# uart_pc.net
KiCad netlist of a schematic drawn in EAGLE
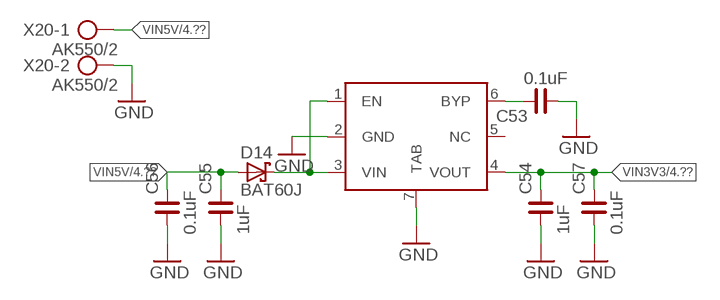
[diagram p0: schematic, sheet 1]
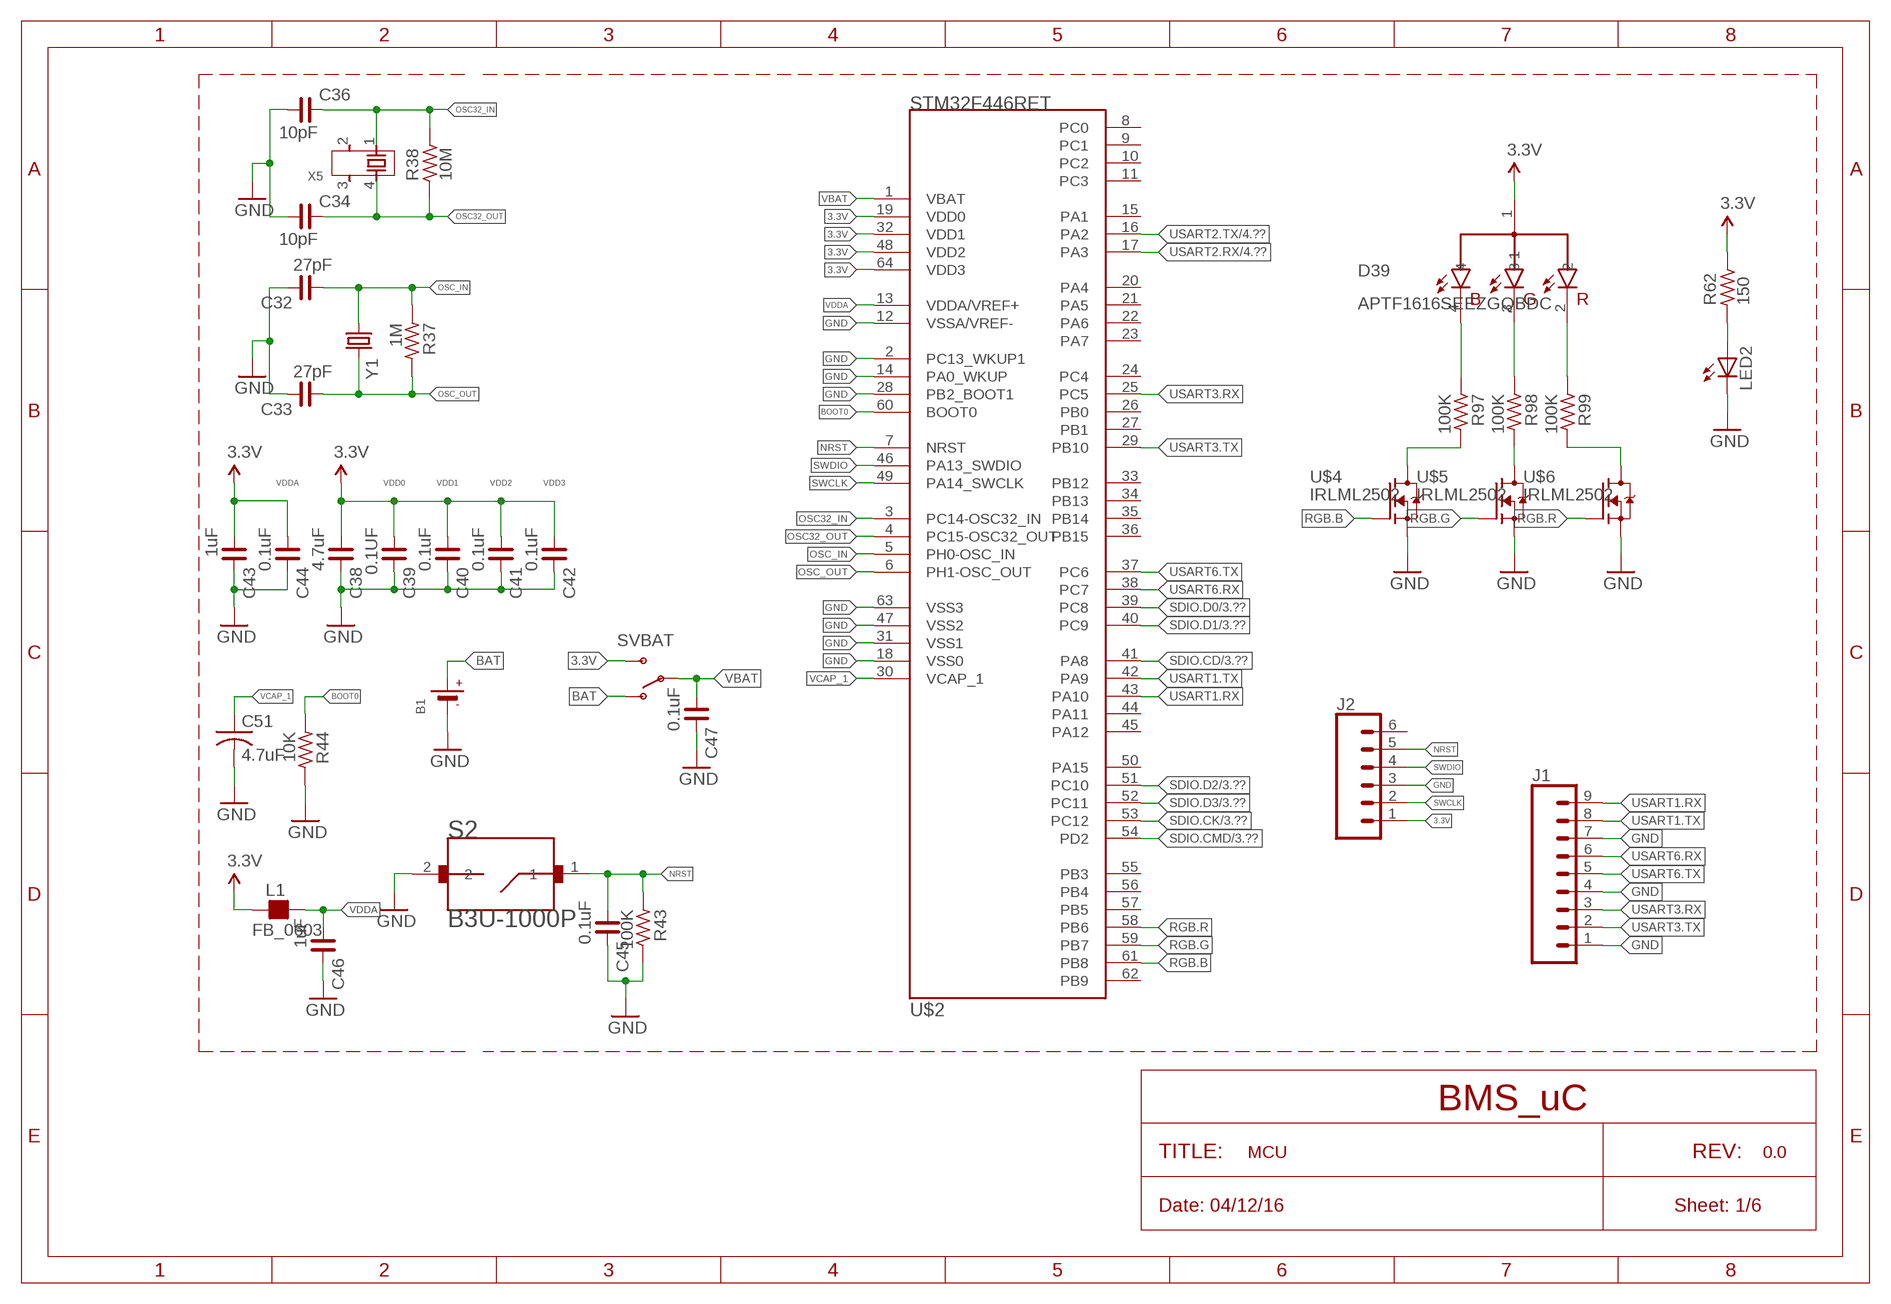
[diagram p1: schematic, sheet 2]
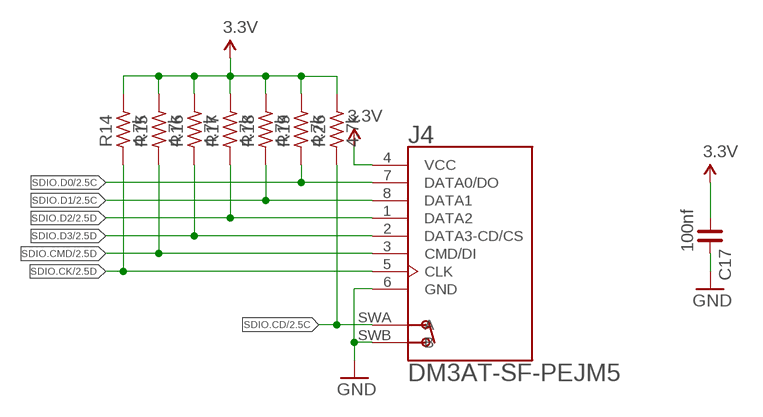
[diagram p2: schematic, sheet 3]
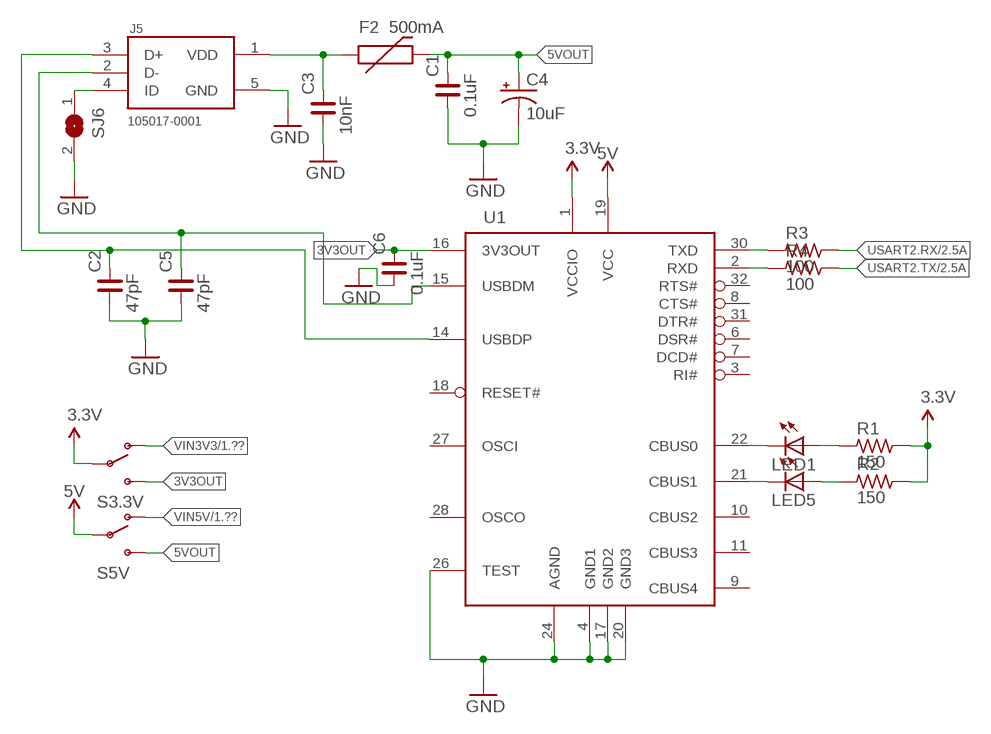
[diagram p3: schematic, sheet 4]

(export (version "E")
  (design (tool "Eeschema 10.0.6"))
  (components
    (comp (ref "C1")
      (value "0.1uF")
      (footprint "eagle-import:C0603")
      (libsource (lib "eagle-import") (part "C_0603"))
    )
    (comp (ref "C2")
      (value "47pF")
      (footprint "eagle-import:C0603")
      (libsource (lib "eagle-import") (part "C_0603"))
    )
    (comp (ref "C3")
      (value "10nF")
      (footprint "eagle-import:C0603")
      (libsource (lib "eagle-import") (part "C_0603"))
    )
    (comp (ref "C4")
      (value "10uF")
      (footprint "eagle-import:EIA3216")
      (libsource (lib "eagle-import") (part "10UF-16V-10%(TANT)"))
    )
    (comp (ref "C5")
      (value "47pF")
      (footprint "eagle-import:C0603")
      (libsource (lib "eagle-import") (part "C_0603"))
    )
    (comp (ref "C6")
      (value "0.1uF")
      (footprint "eagle-import:C0603")
      (libsource (lib "eagle-import") (part "C_0603"))
    )
    (comp (ref "F2")
      (value "500mA")
      (footprint "eagle-import:PTC-1206")
      (libsource (lib "eagle-import") (part "PTCSMD"))
    )
    (comp (ref "J5")
      (value "105017-0001")
      (footprint "eagle-import:MOLEX_105017-0001")
      (fields (field (name "MF") "Molex"))
      (libsource (lib "eagle-import") (part "105017-0001"))
    )
    (comp (ref "LED1")
      (value "LEDCHIPLED_0603")
      (footprint "eagle-import:CHIPLED_0603")
      (libsource (lib "eagle-import") (part "LEDCHIPLED_0603"))
    )
    (comp (ref "LED5")
      (value "LEDCHIPLED_0603")
      (footprint "eagle-import:CHIPLED_0603")
      (libsource (lib "eagle-import") (part "LEDCHIPLED_0603"))
    )
    (comp (ref "R1")
      (value "150")
      (footprint "eagle-import:R0603")
      (libsource (lib "eagle-import") (part "R_0603"))
    )
    (comp (ref "R2")
      (value "150")
      (footprint "eagle-import:R0603")
      (libsource (lib "eagle-import") (part "R_0603"))
    )
    (comp (ref "R3")
      (value "100")
      (footprint "eagle-import:R0603")
      (libsource (lib "eagle-import") (part "R_0603"))
    )
    (comp (ref "R4")
      (value "100")
      (footprint "eagle-import:R0603")
      (libsource (lib "eagle-import") (part "R_0603"))
    )
    (comp (ref "S3.3V")
      (value "SWITCH-SPDTSMD")
      (footprint "eagle-import:AYZ0202")
      (libsource (lib "eagle-import") (part "SWITCH-SPDTSMD"))
    )
    (comp (ref "S5V")
      (value "SWITCH-SPDTSMD")
      (footprint "eagle-import:AYZ0202")
      (libsource (lib "eagle-import") (part "SWITCH-SPDTSMD"))
    )
    (comp (ref "SJ6")
      (value "SOLDERJUMPER")
      (footprint "eagle-import:SOLDERJUMPER_ARROW_NOPASTE")
      (libsource (lib "eagle-import") (part "SOLDERJUMPER"))
    )
    (comp (ref "U1")
      (value "FT232RQ")
      (footprint "eagle-import:LQFP32")
      (fields (field (name "MF") "FTDI"))
      (libsource (lib "eagle-import") (part "FT232RQ"))
    )
    (comp (ref "C53")
      (value "0.1uF")
      (footprint "eagle-import:C0603")
      (libsource (lib "eagle-import") (part "C_0603"))
    )
    (comp (ref "C54")
      (value "1uF")
      (footprint "eagle-import:C0603")
      (libsource (lib "eagle-import") (part "C_0603"))
    )
    (comp (ref "C55")
      (value "1uF")
      (footprint "eagle-import:C0603")
      (libsource (lib "eagle-import") (part "C_0603"))
    )
    (comp (ref "C56")
      (value "0.1uF")
      (footprint "eagle-import:C0603")
      (libsource (lib "eagle-import") (part "C_0603"))
    )
    (comp (ref "C57")
      (value "0.1uF")
      (footprint "eagle-import:C0603")
      (libsource (lib "eagle-import") (part "C_0603"))
    )
    (comp (ref "D14")
      (value "BAT60J")
      (footprint "eagle-import:SOD323_ST")
      (libsource (lib "eagle-import") (part "BAT60J"))
    )
    (comp (ref "U$3")
      (value "MIC5353-3.3YMT-TR")
      (footprint "eagle-import:DFN-6_DC-L")
      (libsource (lib "eagle-import") (part "MIC5353-3.3YMT-TR"))
    )
    (comp (ref "X20")
      (value "AK550/2")
      (footprint "eagle-import:AK550_2")
      (libsource (lib "eagle-import") (part "AK550/2"))
    )
    (comp (ref "C17")
      (value "100nf")
      (footprint "eagle-import:C0603")
      (libsource (lib "eagle-import") (part "C_0603"))
    )
    (comp (ref "J4")
      (value "DM3AT-SF-PEJM5")
      (footprint "eagle-import:HRS_DM3AT-SF-PEJM5")
      (fields (field (name "MF") "Hirose"))
      (libsource (lib "eagle-import") (part "DM3AT-SF-PEJM5"))
    )
    (comp (ref "R14")
      (value "4.7k")
      (footprint "eagle-import:R0603")
      (libsource (lib "eagle-import") (part "R_0603"))
    )
    (comp (ref "R15")
      (value "4.7k")
      (footprint "eagle-import:R0603")
      (libsource (lib "eagle-import") (part "R_0603"))
    )
    (comp (ref "R16")
      (value "4.7k")
      (footprint "eagle-import:R0603")
      (libsource (lib "eagle-import") (part "R_0603"))
    )
    (comp (ref "R17")
      (value "4.7k")
      (footprint "eagle-import:R0603")
      (libsource (lib "eagle-import") (part "R_0603"))
    )
    (comp (ref "R18")
      (value "4.7k")
      (footprint "eagle-import:R0603")
      (libsource (lib "eagle-import") (part "R_0603"))
    )
    (comp (ref "R19")
      (value "4.7k")
      (footprint "eagle-import:R0603")
      (libsource (lib "eagle-import") (part "R_0603"))
    )
    (comp (ref "R26")
      (value "4.7k")
      (footprint "eagle-import:R0603")
      (libsource (lib "eagle-import") (part "R_0603"))
    )
    (comp (ref "B1")
      (value "BATTERYCR1220_SMT")
      (footprint "eagle-import:CR1220")
      (libsource (lib "eagle-import") (part "BATTERYCR1220_SMT"))
    )
    (comp (ref "C32")
      (value "27pF")
      (footprint "eagle-import:C0603")
      (libsource (lib "eagle-import") (part "C_0603"))
    )
    (comp (ref "C33")
      (value "27pF")
      (footprint "eagle-import:C0603")
      (libsource (lib "eagle-import") (part "C_0603"))
    )
    (comp (ref "C34")
      (value "10pF")
      (footprint "eagle-import:C0603")
      (libsource (lib "eagle-import") (part "C_0603"))
    )
    (comp (ref "C36")
      (value "10pF")
      (footprint "eagle-import:C0603")
      (libsource (lib "eagle-import") (part "C_0603"))
    )
    (comp (ref "C38")
      (value "4.7uF")
      (footprint "eagle-import:C0603")
      (libsource (lib "eagle-import") (part "C_0603"))
    )
    (comp (ref "C39")
      (value "0.1UF")
      (footprint "eagle-import:C0603")
      (libsource (lib "eagle-import") (part "C_0603"))
    )
    (comp (ref "C40")
      (value "0.1uF")
      (footprint "eagle-import:C0603")
      (libsource (lib "eagle-import") (part "C_0603"))
    )
    (comp (ref "C41")
      (value "0.1uF")
      (footprint "eagle-import:C0603")
      (libsource (lib "eagle-import") (part "C_0603"))
    )
    (comp (ref "C42")
      (value "0.1uF")
      (footprint "eagle-import:C0603")
      (libsource (lib "eagle-import") (part "C_0603"))
    )
    (comp (ref "C43")
      (value "1uF")
      (footprint "eagle-import:C0603")
      (libsource (lib "eagle-import") (part "C_0603"))
    )
    (comp (ref "C44")
      (value "0.1uF")
      (footprint "eagle-import:C0603")
      (libsource (lib "eagle-import") (part "C_0603"))
    )
    (comp (ref "C45")
      (value "0.1uF")
      (footprint "eagle-import:C0603")
      (libsource (lib "eagle-import") (part "C_0603"))
    )
    (comp (ref "C46")
      (value "1uF")
      (footprint "eagle-import:C0603")
      (libsource (lib "eagle-import") (part "C_0603"))
    )
    (comp (ref "C47")
      (value "0.1uF")
      (footprint "eagle-import:C0603")
      (libsource (lib "eagle-import") (part "C_0603"))
    )
    (comp (ref "C51")
      (value "4.7uF")
      (footprint "eagle-import:C1206")
      (libsource (lib "eagle-import") (part "C-USC1206"))
    )
    (comp (ref "D39")
      (value "APTF1616SEEZGQBDC")
      (footprint "eagle-import:0606(1616)")
      (fields (field (name "MF") "Lumex") (field (name "MP") "SML-LX0404SIUPGUSB"))
      (libsource (lib "eagle-import") (part "APTF1616SEEZGQBDC"))
    )
    (comp (ref "J1")
      (value "CONN_09")
      (footprint "eagle-import:1X09")
      (libsource (lib "eagle-import") (part "CONN_09"))
    )
    (comp (ref "J2")
      (value "CONN_06SILK_FEMALE_PTH")
      (footprint "eagle-import:1X06")
      (libsource (lib "eagle-import") (part "CONN_06SILK_FEMALE_PTH"))
    )
    (comp (ref "L1")
      (value "FB_0603")
      (footprint "eagle-import:L0603")
      (libsource (lib "eagle-import") (part "FB_0603"))
    )
    (comp (ref "LED2")
      (value "LEDCHIP-LED0603")
      (footprint "eagle-import:CHIP-LED0603")
      (libsource (lib "eagle-import") (part "LEDCHIP-LED0603"))
    )
    (comp (ref "R37")
      (value "1M")
      (footprint "eagle-import:R0603")
      (libsource (lib "eagle-import") (part "R_0603"))
    )
    (comp (ref "R38")
      (value "10M")
      (footprint "eagle-import:R0603")
      (libsource (lib "eagle-import") (part "R_0603"))
    )
    (comp (ref "R43")
      (value "100K")
      (footprint "eagle-import:R0603")
      (libsource (lib "eagle-import") (part "R_0603"))
    )
    (comp (ref "R44")
      (value "10K")
      (footprint "eagle-import:R0603")
      (libsource (lib "eagle-import") (part "R_0603"))
    )
    (comp (ref "R62")
      (value "150")
      (footprint "eagle-import:R0603")
      (libsource (lib "eagle-import") (part "R_0603"))
    )
    (comp (ref "R97")
      (value "100K")
      (footprint "eagle-import:R0603")
      (libsource (lib "eagle-import") (part "R_0603"))
    )
    (comp (ref "R98")
      (value "100K")
      (footprint "eagle-import:R0603")
      (libsource (lib "eagle-import") (part "R_0603"))
    )
    (comp (ref "R99")
      (value "100K")
      (footprint "eagle-import:R0603")
      (libsource (lib "eagle-import") (part "R_0603"))
    )
    (comp (ref "S2")
      (value "B3U-1000P")
      (footprint "eagle-import:SW_B3U-1000P")
      (fields (field (name "MF") "Omron"))
      (libsource (lib "eagle-import") (part "B3U-1000P"))
    )
    (comp (ref "SVBAT")
      (value "SWITCH-SPDTSMD")
      (footprint "eagle-import:AYZ0202")
      (libsource (lib "eagle-import") (part "SWITCH-SPDTSMD"))
    )
    (comp (ref "U$2")
      (value "STM32F446RET")
      (footprint "eagle-import:LQFP64")
      (libsource (lib "eagle-import") (part "STM32F446RET"))
    )
    (comp (ref "U$4")
      (value "IRLML2502")
      (footprint "eagle-import:SOT23")
      (fields (field (name "MF") "International Rectifier"))
      (libsource (lib "eagle-import") (part "IRLML2502"))
    )
    (comp (ref "U$5")
      (value "IRLML2502")
      (footprint "eagle-import:SOT23")
      (fields (field (name "MF") "International Rectifier"))
      (libsource (lib "eagle-import") (part "IRLML2502"))
    )
    (comp (ref "U$6")
      (value "IRLML2502")
      (footprint "eagle-import:SOT23")
      (fields (field (name "MF") "International Rectifier"))
      (libsource (lib "eagle-import") (part "IRLML2502"))
    )
    (comp (ref "X5")
      (value "CRYSTAL-4PIN")
      (footprint "eagle-import:ABRACON-ABS25-32.768KHZ")
      (libsource (lib "eagle-import") (part "CRYSTAL-4PIN"))
    )
    (comp (ref "Y1")
      (value "CRYSTALSMD")
      (footprint "eagle-import:HC49UP")
      (libsource (lib "eagle-import") (part "CRYSTALSMD"))
    )
  )
  (nets
    (net (code "1") (name "3.3V") (class "Default")
      (node (ref "C17") (pin "1") (pinfunction "1_1") (pintype "passive"))
      (node (ref "C38") (pin "1") (pinfunction "1_1") (pintype "passive"))
      (node (ref "C39") (pin "1") (pinfunction "1_1") (pintype "passive"))
      (node (ref "C40") (pin "1") (pinfunction "1_1") (pintype "passive"))
      (node (ref "C41") (pin "1") (pinfunction "1_1") (pintype "passive"))
      (node (ref "C42") (pin "1") (pinfunction "1_1") (pintype "passive"))
      (node (ref "C43") (pin "1") (pinfunction "1_1") (pintype "passive"))
      (node (ref "C44") (pin "1") (pinfunction "1_1") (pintype "passive"))
      (node (ref "D39") (pin "1") (pinfunction "1_1") (pintype "passive"))
      (node (ref "J2") (pin "1") (pinfunction "1_1") (pintype "passive"))
      (node (ref "J4") (pin "4") (pinfunction "VCC_4") (pintype "power_in"))
      (node (ref "L1") (pin "1") (pinfunction "1_1") (pintype "passive"))
      (node (ref "R1") (pin "2") (pinfunction "2_2") (pintype "passive"))
      (node (ref "R14") (pin "2") (pinfunction "2_2") (pintype "passive"))
      (node (ref "R15") (pin "2") (pinfunction "2_2") (pintype "passive"))
      (node (ref "R16") (pin "2") (pinfunction "2_2") (pintype "passive"))
      (node (ref "R17") (pin "2") (pinfunction "2_2") (pintype "passive"))
      (node (ref "R18") (pin "2") (pinfunction "2_2") (pintype "passive"))
      (node (ref "R19") (pin "2") (pinfunction "2_2") (pintype "passive"))
      (node (ref "R2") (pin "2") (pinfunction "2_2") (pintype "passive"))
      (node (ref "R26") (pin "2") (pinfunction "2_2") (pintype "passive"))
      (node (ref "R62") (pin "2") (pinfunction "2_2") (pintype "passive"))
      (node (ref "S3.3V") (pin "2") (pinfunction "P_2") (pintype "passive"))
      (node (ref "SVBAT") (pin "3") (pinfunction "S_3") (pintype "passive"))
      (node (ref "U$2") (pin "19") (pinfunction "VDD0_19") (pintype "power_in"))
      (node (ref "U$2") (pin "32") (pinfunction "VDD1_32") (pintype "power_in"))
      (node (ref "U$2") (pin "48") (pinfunction "VDD2_48") (pintype "power_in"))
      (node (ref "U$2") (pin "64") (pinfunction "VDD3_64") (pintype "power_in"))
      (node (ref "U1") (pin "1") (pinfunction "VCCIO_1") (pintype "power_in"))
    )
    (net (code "2") (name "3V3OUT") (class "Default")
      (node (ref "C6") (pin "2") (pinfunction "2_2") (pintype "passive"))
      (node (ref "S3.3V") (pin "3") (pinfunction "S_3") (pintype "passive"))
      (node (ref "U1") (pin "16") (pinfunction "3V3OUT_16") (pintype "output"))
    )
    (net (code "3") (name "5V") (class "Default")
      (node (ref "S5V") (pin "2") (pinfunction "P_2") (pintype "passive"))
      (node (ref "U1") (pin "19") (pinfunction "VCC_19") (pintype "power_in"))
    )
    (net (code "4") (name "5VOUT") (class "Default")
      (node (ref "C1") (pin "2") (pinfunction "2_2") (pintype "passive"))
      (node (ref "C4") (pin "A") (pinfunction "+_A") (pintype "passive"))
      (node (ref "F2") (pin "2") (pinfunction "2_2") (pintype "bidirectional"))
      (node (ref "S5V") (pin "3") (pinfunction "S_3") (pintype "passive"))
    )
    (net (code "5") (name "BAT") (class "Default")
      (node (ref "B1") (pin "+$1") (pinfunction "+_+$1") (pintype "passive"))
      (node (ref "SVBAT") (pin "1") (pinfunction "O_1") (pintype "passive"))
    )
    (net (code "6") (name "BOOT0") (class "Default")
      (node (ref "R44") (pin "1") (pinfunction "1_1") (pintype "passive"))
      (node (ref "U$2") (pin "60") (pinfunction "BOOT0_60") (pintype "input"))
    )
    (net (code "7") (name "GND") (class "Default")
      (node (ref "B1") (pin "-") (pinfunction "-_-") (pintype "passive"))
      (node (ref "C1") (pin "1") (pinfunction "1_1") (pintype "passive"))
      (node (ref "C17") (pin "2") (pinfunction "2_2") (pintype "passive"))
      (node (ref "C2") (pin "1") (pinfunction "1_1") (pintype "passive"))
      (node (ref "C3") (pin "1") (pinfunction "1_1") (pintype "passive"))
      (node (ref "C32") (pin "2") (pinfunction "2_2") (pintype "passive"))
      (node (ref "C33") (pin "2") (pinfunction "2_2") (pintype "passive"))
      (node (ref "C34") (pin "1") (pinfunction "1_1") (pintype "passive"))
      (node (ref "C36") (pin "1") (pinfunction "1_1") (pintype "passive"))
      (node (ref "C38") (pin "2") (pinfunction "2_2") (pintype "passive"))
      (node (ref "C39") (pin "2") (pinfunction "2_2") (pintype "passive"))
      (node (ref "C4") (pin "C") (pinfunction "-_C") (pintype "passive"))
      (node (ref "C40") (pin "2") (pinfunction "2_2") (pintype "passive"))
      (node (ref "C41") (pin "2") (pinfunction "2_2") (pintype "passive"))
      (node (ref "C42") (pin "2") (pinfunction "2_2") (pintype "passive"))
      (node (ref "C43") (pin "2") (pinfunction "2_2") (pintype "passive"))
      (node (ref "C44") (pin "2") (pinfunction "2_2") (pintype "passive"))
      (node (ref "C45") (pin "2") (pinfunction "2_2") (pintype "passive"))
      (node (ref "C46") (pin "2") (pinfunction "2_2") (pintype "passive"))
      (node (ref "C47") (pin "2") (pinfunction "2_2") (pintype "passive"))
      (node (ref "C5") (pin "1") (pinfunction "1_1") (pintype "passive"))
      (node (ref "C51") (pin "2") (pinfunction "2_2") (pintype "passive"))
      (node (ref "C53") (pin "1") (pinfunction "1_1") (pintype "passive"))
      (node (ref "C54") (pin "1") (pinfunction "1_1") (pintype "passive"))
      (node (ref "C55") (pin "1") (pinfunction "1_1") (pintype "passive"))
      (node (ref "C56") (pin "1") (pinfunction "1_1") (pintype "passive"))
      (node (ref "C57") (pin "1") (pinfunction "1_1") (pintype "passive"))
      (node (ref "C6") (pin "1") (pinfunction "1_1") (pintype "passive"))
      (node (ref "J1") (pin "1") (pinfunction "1_1") (pintype "passive"))
      (node (ref "J1") (pin "4") (pinfunction "4_4") (pintype "passive"))
      (node (ref "J1") (pin "7") (pinfunction "7_7") (pintype "passive"))
      (node (ref "J2") (pin "3") (pinfunction "3_3") (pintype "passive"))
      (node (ref "J4") (pin "6") (pinfunction "GND_6") (pintype "power_in"))
      (node (ref "J4") (pin "SWB") (pinfunction "B_SWB") (pintype "bidirectional"))
      (node (ref "J5") (pin "5") (pinfunction "GND_5") (pintype "power_in"))
      (node (ref "LED2") (pin "C") (pinfunction "C_C") (pintype "passive"))
      (node (ref "R43") (pin "2") (pinfunction "2_2") (pintype "passive"))
      (node (ref "R44") (pin "2") (pinfunction "2_2") (pintype "passive"))
      (node (ref "S2") (pin "2") (pinfunction "2_2") (pintype "passive"))
      (node (ref "SJ6") (pin "2") (pinfunction "2_2") (pintype "passive"))
      (node (ref "U$2") (pin "12") (pinfunction "VSSA/VREF-_12") (pintype "power_in"))
      (node (ref "U$2") (pin "14") (pinfunction "PA0_WKUP_14") (pintype "bidirectional"))
      (node (ref "U$2") (pin "18") (pinfunction "VSS0_18") (pintype "power_in"))
      (node (ref "U$2") (pin "2") (pinfunction "PC13_WKUP1_2") (pintype "bidirectional"))
      (node (ref "U$2") (pin "28") (pinfunction "PB2_BOOT1_28") (pintype "bidirectional"))
      (node (ref "U$2") (pin "31") (pinfunction "VSS1_31") (pintype "power_in"))
      (node (ref "U$2") (pin "47") (pinfunction "VSS2_47") (pintype "power_in"))
      (node (ref "U$2") (pin "63") (pinfunction "VSS3_63") (pintype "power_in"))
      (node (ref "U$3") (pin "2") (pinfunction "GND_2") (pintype "power_in"))
      (node (ref "U$3") (pin "7") (pinfunction "TAB_7") (pintype "power_in"))
      (node (ref "U$4") (pin "2") (pinfunction "S_2") (pintype "passive"))
      (node (ref "U$5") (pin "2") (pinfunction "S_2") (pintype "passive"))
      (node (ref "U$6") (pin "2") (pinfunction "S_2") (pintype "passive"))
      (node (ref "U1") (pin "17") (pinfunction "GND2_17") (pintype "power_in"))
      (node (ref "U1") (pin "20") (pinfunction "GND3_20") (pintype "power_in"))
      (node (ref "U1") (pin "24") (pinfunction "AGND_24") (pintype "power_in"))
      (node (ref "U1") (pin "26") (pinfunction "TEST_26") (pintype "input"))
      (node (ref "U1") (pin "4") (pinfunction "GND1_4") (pintype "power_in"))
      (node (ref "X20") (pin "2") (pinfunction "KL_2") (pintype "passive"))
    )
    (net (code "8") (name "NRST") (class "Default")
      (node (ref "C45") (pin "1") (pinfunction "1_1") (pintype "passive"))
      (node (ref "J2") (pin "5") (pinfunction "5_5") (pintype "passive"))
      (node (ref "R43") (pin "1") (pinfunction "1_1") (pintype "passive"))
      (node (ref "S2") (pin "1") (pinfunction "1_1") (pintype "passive"))
      (node (ref "U$2") (pin "7") (pinfunction "NRST_7") (pintype "bidirectional"))
    )
    (net (code "9") (name "Net-(D39-Pad2)") (class "Default")
      (node (ref "D39") (pin "2") (pinfunction "2_2") (pintype "passive"))
      (node (ref "R99") (pin "1") (pinfunction "1_1") (pintype "passive"))
    )
    (net (code "10") (name "Net-(D39-Pad3)") (class "Default")
      (node (ref "D39") (pin "3") (pinfunction "3_3") (pintype "passive"))
      (node (ref "R98") (pin "1") (pinfunction "1_1") (pintype "passive"))
    )
    (net (code "11") (name "Net-(D39-Pad4)") (class "Default")
      (node (ref "D39") (pin "4") (pinfunction "4_4") (pintype "passive"))
      (node (ref "R97") (pin "1") (pinfunction "1_1") (pintype "passive"))
    )
    (net (code "12") (name "Net-(J5-D+)") (class "Default")
      (node (ref "C2") (pin "2") (pinfunction "2_2") (pintype "passive"))
      (node (ref "J5") (pin "3") (pinfunction "D+_3") (pintype "bidirectional"))
      (node (ref "U1") (pin "14") (pinfunction "USBDP_14") (pintype "bidirectional"))
    )
    (net (code "13") (name "Net-(J5-D-)") (class "Default")
      (node (ref "C5") (pin "2") (pinfunction "2_2") (pintype "passive"))
      (node (ref "J5") (pin "2") (pinfunction "D-_2") (pintype "bidirectional"))
      (node (ref "U1") (pin "15") (pinfunction "USBDM_15") (pintype "bidirectional"))
    )
    (net (code "14") (name "Net-(J5-ID)") (class "Default")
      (node (ref "J5") (pin "4") (pinfunction "ID_4") (pintype "passive"))
      (node (ref "SJ6") (pin "1") (pinfunction "1_1") (pintype "passive"))
    )
    (net (code "15") (name "Net-(J5-VDD)") (class "Default")
      (node (ref "C3") (pin "2") (pinfunction "2_2") (pintype "passive"))
      (node (ref "F2") (pin "1") (pinfunction "1_1") (pintype "bidirectional"))
      (node (ref "J5") (pin "1") (pinfunction "VDD_1") (pintype "power_in"))
    )
    (net (code "16") (name "Net-(LED1-PadA)") (class "Default")
      (node (ref "LED1") (pin "A") (pinfunction "A_A") (pintype "passive"))
      (node (ref "R1") (pin "1") (pinfunction "1_1") (pintype "passive"))
    )
    (net (code "17") (name "Net-(LED2-PadA)") (class "Default")
      (node (ref "LED2") (pin "A") (pinfunction "A_A") (pintype "passive"))
      (node (ref "R62") (pin "1") (pinfunction "1_1") (pintype "passive"))
    )
    (net (code "18") (name "Net-(LED5-PadA)") (class "Default")
      (node (ref "LED5") (pin "A") (pinfunction "A_A") (pintype "passive"))
      (node (ref "R2") (pin "1") (pinfunction "1_1") (pintype "passive"))
    )
    (net (code "19") (name "Net-(U$3-BYP)") (class "Default")
      (node (ref "C53") (pin "2") (pinfunction "2_2") (pintype "passive"))
      (node (ref "U$3") (pin "6") (pinfunction "BYP_6") (pintype "passive"))
    )
    (net (code "20") (name "Net-(U$3-EN)") (class "Default")
      (node (ref "D14") (pin "C") (pinfunction "C_C") (pintype "passive"))
      (node (ref "U$3") (pin "1") (pinfunction "EN_1") (pintype "passive"))
      (node (ref "U$3") (pin "3") (pinfunction "VIN_3") (pintype "power_in"))
    )
    (net (code "21") (name "Net-(U$4-D)") (class "Default")
      (node (ref "R97") (pin "2") (pinfunction "2_2") (pintype "passive"))
      (node (ref "U$4") (pin "3") (pinfunction "D_3") (pintype "passive"))
    )
    (net (code "22") (name "Net-(U$5-D)") (class "Default")
      (node (ref "R98") (pin "2") (pinfunction "2_2") (pintype "passive"))
      (node (ref "U$5") (pin "3") (pinfunction "D_3") (pintype "passive"))
    )
    (net (code "23") (name "Net-(U$6-D)") (class "Default")
      (node (ref "R99") (pin "2") (pinfunction "2_2") (pintype "passive"))
      (node (ref "U$6") (pin "3") (pinfunction "D_3") (pintype "passive"))
    )
    (net (code "24") (name "Net-(U1-CBUS0)") (class "Default")
      (node (ref "LED1") (pin "C") (pinfunction "C_C") (pintype "passive"))
      (node (ref "U1") (pin "22") (pinfunction "CBUS0_22") (pintype "bidirectional"))
    )
    (net (code "25") (name "Net-(U1-CBUS1)") (class "Default")
      (node (ref "LED5") (pin "C") (pinfunction "C_C") (pintype "passive"))
      (node (ref "U1") (pin "21") (pinfunction "CBUS1_21") (pintype "bidirectional"))
    )
    (net (code "26") (name "Net-(U1-RXD)") (class "Default")
      (node (ref "R4") (pin "1") (pinfunction "1_1") (pintype "passive"))
      (node (ref "U1") (pin "2") (pinfunction "RXD_2") (pintype "input"))
    )
    (net (code "27") (name "Net-(U1-TXD)") (class "Default")
      (node (ref "R3") (pin "1") (pinfunction "1_1") (pintype "passive"))
      (node (ref "U1") (pin "30") (pinfunction "TXD_30") (pintype "output"))
    )
    (net (code "28") (name "OSC32_IN") (class "Default")
      (node (ref "C36") (pin "2") (pinfunction "2_2") (pintype "passive"))
      (node (ref "R38") (pin "2") (pinfunction "2_2") (pintype "passive"))
      (node (ref "U$2") (pin "3") (pinfunction "PC14-OSC32_IN_3") (pintype "bidirectional"))
      (node (ref "X5") (pin "1") (pinfunction "1_1") (pintype "bidirectional"))
    )
    (net (code "29") (name "OSC32_OUT") (class "Default")
      (node (ref "C34") (pin "2") (pinfunction "2_2") (pintype "passive"))
      (node (ref "R38") (pin "1") (pinfunction "1_1") (pintype "passive"))
      (node (ref "U$2") (pin "4") (pinfunction "PC15-OSC32_OUT_4") (pintype "bidirectional"))
      (node (ref "X5") (pin "4") (pinfunction "4_4") (pintype "bidirectional"))
    )
    (net (code "30") (name "OSC_IN") (class "Default")
      (node (ref "C32") (pin "1") (pinfunction "1_1") (pintype "passive"))
      (node (ref "R37") (pin "1") (pinfunction "1_1") (pintype "passive"))
      (node (ref "U$2") (pin "5") (pinfunction "PH0-OSC_IN_5") (pintype "bidirectional"))
      (node (ref "Y1") (pin "1") (pinfunction "1_1") (pintype "passive"))
    )
    (net (code "31") (name "OSC_OUT") (class "Default")
      (node (ref "C33") (pin "1") (pinfunction "1_1") (pintype "passive"))
      (node (ref "R37") (pin "2") (pinfunction "2_2") (pintype "passive"))
      (node (ref "U$2") (pin "6") (pinfunction "PH1-OSC_OUT_6") (pintype "bidirectional"))
      (node (ref "Y1") (pin "2") (pinfunction "2_2") (pintype "passive"))
    )
    (net (code "32") (name "RGB.B") (class "Default")
      (node (ref "U$2") (pin "61") (pinfunction "PB8_61") (pintype "bidirectional"))
      (node (ref "U$4") (pin "1") (pinfunction "G_1") (pintype "passive"))
    )
    (net (code "33") (name "RGB.G") (class "Default")
      (node (ref "U$2") (pin "59") (pinfunction "PB7_59") (pintype "bidirectional"))
      (node (ref "U$5") (pin "1") (pinfunction "G_1") (pintype "passive"))
    )
    (net (code "34") (name "RGB.R") (class "Default")
      (node (ref "U$2") (pin "58") (pinfunction "PB6_58") (pintype "bidirectional"))
      (node (ref "U$6") (pin "1") (pinfunction "G_1") (pintype "passive"))
    )
    (net (code "35") (name "SDIO.CD") (class "Default")
      (node (ref "J4") (pin "SWA") (pinfunction "A_SWA") (pintype "bidirectional"))
      (node (ref "R26") (pin "1") (pinfunction "1_1") (pintype "passive"))
      (node (ref "U$2") (pin "41") (pinfunction "PA8_41") (pintype "bidirectional"))
    )
    (net (code "36") (name "SDIO.CK") (class "Default")
      (node (ref "J4") (pin "5") (pinfunction "CLK_5") (pintype "bidirectional"))
      (node (ref "R14") (pin "1") (pinfunction "1_1") (pintype "passive"))
      (node (ref "U$2") (pin "53") (pinfunction "PC12_53") (pintype "bidirectional"))
    )
    (net (code "37") (name "SDIO.CMD") (class "Default")
      (node (ref "J4") (pin "3") (pinfunction "CMD/DI_3") (pintype "bidirectional"))
      (node (ref "R15") (pin "1") (pinfunction "1_1") (pintype "passive"))
      (node (ref "U$2") (pin "54") (pinfunction "PD2_54") (pintype "bidirectional"))
    )
    (net (code "38") (name "SDIO.D0") (class "Default")
      (node (ref "J4") (pin "7") (pinfunction "DATA0/DO_7") (pintype "bidirectional"))
      (node (ref "R19") (pin "1") (pinfunction "1_1") (pintype "passive"))
      (node (ref "U$2") (pin "39") (pinfunction "PC8_39") (pintype "bidirectional"))
    )
    (net (code "39") (name "SDIO.D1") (class "Default")
      (node (ref "J4") (pin "8") (pinfunction "DATA1_8") (pintype "bidirectional"))
      (node (ref "R18") (pin "1") (pinfunction "1_1") (pintype "passive"))
      (node (ref "U$2") (pin "40") (pinfunction "PC9_40") (pintype "bidirectional"))
    )
    (net (code "40") (name "SDIO.D2") (class "Default")
      (node (ref "J4") (pin "1") (pinfunction "DATA2_1") (pintype "bidirectional"))
      (node (ref "R17") (pin "1") (pinfunction "1_1") (pintype "passive"))
      (node (ref "U$2") (pin "51") (pinfunction "PC10_51") (pintype "bidirectional"))
    )
    (net (code "41") (name "SDIO.D3") (class "Default")
      (node (ref "J4") (pin "2") (pinfunction "DATA3-CD/CS_2") (pintype "bidirectional"))
      (node (ref "R16") (pin "1") (pinfunction "1_1") (pintype "passive"))
      (node (ref "U$2") (pin "52") (pinfunction "PC11_52") (pintype "bidirectional"))
    )
    (net (code "42") (name "SWCLK") (class "Default")
      (node (ref "J2") (pin "2") (pinfunction "2_2") (pintype "passive"))
      (node (ref "U$2") (pin "49") (pinfunction "PA14_SWCLK_49") (pintype "bidirectional"))
    )
    (net (code "43") (name "SWDIO") (class "Default")
      (node (ref "J2") (pin "4") (pinfunction "4_4") (pintype "passive"))
      (node (ref "U$2") (pin "46") (pinfunction "PA13_SWDIO_46") (pintype "bidirectional"))
    )
    (net (code "44") (name "USART1.RX") (class "Default")
      (node (ref "J1") (pin "9") (pinfunction "9_9") (pintype "passive"))
      (node (ref "U$2") (pin "43") (pinfunction "PA10_43") (pintype "bidirectional"))
    )
    (net (code "45") (name "USART1.TX") (class "Default")
      (node (ref "J1") (pin "8") (pinfunction "8_8") (pintype "passive"))
      (node (ref "U$2") (pin "42") (pinfunction "PA9_42") (pintype "bidirectional"))
    )
    (net (code "46") (name "USART2.RX") (class "Default")
      (node (ref "R3") (pin "2") (pinfunction "2_2") (pintype "passive"))
      (node (ref "U$2") (pin "17") (pinfunction "PA3_17") (pintype "bidirectional"))
    )
    (net (code "47") (name "USART2.TX") (class "Default")
      (node (ref "R4") (pin "2") (pinfunction "2_2") (pintype "passive"))
      (node (ref "U$2") (pin "16") (pinfunction "PA2_16") (pintype "bidirectional"))
    )
    (net (code "48") (name "USART3.RX") (class "Default")
      (node (ref "J1") (pin "3") (pinfunction "3_3") (pintype "passive"))
      (node (ref "U$2") (pin "25") (pinfunction "PC5_25") (pintype "bidirectional"))
    )
    (net (code "49") (name "USART3.TX") (class "Default")
      (node (ref "J1") (pin "2") (pinfunction "2_2") (pintype "passive"))
      (node (ref "U$2") (pin "29") (pinfunction "PB10_29") (pintype "bidirectional"))
    )
    (net (code "50") (name "USART6.RX") (class "Default")
      (node (ref "J1") (pin "6") (pinfunction "6_6") (pintype "passive"))
      (node (ref "U$2") (pin "38") (pinfunction "PC7_38") (pintype "bidirectional"))
    )
    (net (code "51") (name "USART6.TX") (class "Default")
      (node (ref "J1") (pin "5") (pinfunction "5_5") (pintype "passive"))
      (node (ref "U$2") (pin "37") (pinfunction "PC6_37") (pintype "bidirectional"))
    )
    (net (code "52") (name "VBAT") (class "Default")
      (node (ref "C47") (pin "1") (pinfunction "1_1") (pintype "passive"))
      (node (ref "SVBAT") (pin "2") (pinfunction "P_2") (pintype "passive"))
      (node (ref "U$2") (pin "1") (pinfunction "VBAT_1") (pintype "power_in"))
    )
    (net (code "53") (name "VCAP_1") (class "Default")
      (node (ref "C51") (pin "1") (pinfunction "1_1") (pintype "passive"))
      (node (ref "U$2") (pin "30") (pinfunction "VCAP_1_30") (pintype "power_in"))
    )
    (net (code "54") (name "VDDA") (class "Default")
      (node (ref "C46") (pin "1") (pinfunction "1_1") (pintype "passive"))
      (node (ref "L1") (pin "2") (pinfunction "2_2") (pintype "passive"))
      (node (ref "U$2") (pin "13") (pinfunction "VDDA/VREF+_13") (pintype "power_in"))
    )
    (net (code "55") (name "VIN3V3") (class "Default")
      (node (ref "C54") (pin "2") (pinfunction "2_2") (pintype "passive"))
      (node (ref "C57") (pin "2") (pinfunction "2_2") (pintype "passive"))
      (node (ref "S3.3V") (pin "1") (pinfunction "O_1") (pintype "passive"))
      (node (ref "U$3") (pin "4") (pinfunction "VOUT_4") (pintype "power_in"))
    )
    (net (code "56") (name "VIN5V") (class "Default")
      (node (ref "C55") (pin "2") (pinfunction "2_2") (pintype "passive"))
      (node (ref "C56") (pin "2") (pinfunction "2_2") (pintype "passive"))
      (node (ref "D14") (pin "A") (pinfunction "A_A") (pintype "passive"))
      (node (ref "S5V") (pin "1") (pinfunction "O_1") (pintype "passive"))
      (node (ref "X20") (pin "1") (pinfunction "KL_1") (pintype "passive"))
    )
    (net (code "57") (name "unconnected-(J2-Pad6)") (class "Default")
      (node (ref "J2") (pin "6") (pinfunction "6_6") (pintype "passive"))
    )
    (net (code "58") (name "unconnected-(U$2-PA1-Pad15)") (class "Default")
      (node (ref "U$2") (pin "15") (pinfunction "PA1_15") (pintype "bidirectional"))
    )
    (net (code "59") (name "unconnected-(U$2-PA4-Pad20)") (class "Default")
      (node (ref "U$2") (pin "20") (pinfunction "PA4_20") (pintype "bidirectional"))
    )
    (net (code "60") (name "unconnected-(U$2-PA5-Pad21)") (class "Default")
      (node (ref "U$2") (pin "21") (pinfunction "PA5_21") (pintype "bidirectional"))
    )
    (net (code "61") (name "unconnected-(U$2-PA6-Pad22)") (class "Default")
      (node (ref "U$2") (pin "22") (pinfunction "PA6_22") (pintype "bidirectional"))
    )
    (net (code "62") (name "unconnected-(U$2-PA7-Pad23)") (class "Default")
      (node (ref "U$2") (pin "23") (pinfunction "PA7_23") (pintype "bidirectional"))
    )
    (net (code "63") (name "unconnected-(U$2-PA11-Pad44)") (class "Default")
      (node (ref "U$2") (pin "44") (pinfunction "PA11_44") (pintype "bidirectional"))
    )
    (net (code "64") (name "unconnected-(U$2-PA12-Pad45)") (class "Default")
      (node (ref "U$2") (pin "45") (pinfunction "PA12_45") (pintype "bidirectional"))
    )
    (net (code "65") (name "unconnected-(U$2-PA15-Pad50)") (class "Default")
      (node (ref "U$2") (pin "50") (pinfunction "PA15_50") (pintype "bidirectional"))
    )
    (net (code "66") (name "unconnected-(U$2-PB0-Pad26)") (class "Default")
      (node (ref "U$2") (pin "26") (pinfunction "PB0_26") (pintype "bidirectional"))
    )
    (net (code "67") (name "unconnected-(U$2-PB1-Pad27)") (class "Default")
      (node (ref "U$2") (pin "27") (pinfunction "PB1_27") (pintype "bidirectional"))
    )
    (net (code "68") (name "unconnected-(U$2-PB3-Pad55)") (class "Default")
      (node (ref "U$2") (pin "55") (pinfunction "PB3_55") (pintype "bidirectional"))
    )
    (net (code "69") (name "unconnected-(U$2-PB4-Pad56)") (class "Default")
      (node (ref "U$2") (pin "56") (pinfunction "PB4_56") (pintype "input"))
    )
    (net (code "70") (name "unconnected-(U$2-PB5-Pad57)") (class "Default")
      (node (ref "U$2") (pin "57") (pinfunction "PB5_57") (pintype "bidirectional"))
    )
    (net (code "71") (name "unconnected-(U$2-PB9-Pad62)") (class "Default")
      (node (ref "U$2") (pin "62") (pinfunction "PB9_62") (pintype "bidirectional"))
    )
    (net (code "72") (name "unconnected-(U$2-PB12-Pad33)") (class "Default")
      (node (ref "U$2") (pin "33") (pinfunction "PB12_33") (pintype "bidirectional"))
    )
    (net (code "73") (name "unconnected-(U$2-PB13-Pad34)") (class "Default")
      (node (ref "U$2") (pin "34") (pinfunction "PB13_34") (pintype "bidirectional"))
    )
    (net (code "74") (name "unconnected-(U$2-PB14-Pad35)") (class "Default")
      (node (ref "U$2") (pin "35") (pinfunction "PB14_35") (pintype "bidirectional"))
    )
    (net (code "75") (name "unconnected-(U$2-PB15-Pad36)") (class "Default")
      (node (ref "U$2") (pin "36") (pinfunction "PB15_36") (pintype "bidirectional"))
    )
    (net (code "76") (name "unconnected-(U$2-PC0-Pad8)") (class "Default")
      (node (ref "U$2") (pin "8") (pinfunction "PC0_8") (pintype "bidirectional"))
    )
    (net (code "77") (name "unconnected-(U$2-PC1-Pad9)") (class "Default")
      (node (ref "U$2") (pin "9") (pinfunction "PC1_9") (pintype "bidirectional"))
    )
    (net (code "78") (name "unconnected-(U$2-PC2-Pad10)") (class "Default")
      (node (ref "U$2") (pin "10") (pinfunction "PC2_10") (pintype "bidirectional"))
    )
    (net (code "79") (name "unconnected-(U$2-PC3-Pad11)") (class "Default")
      (node (ref "U$2") (pin "11") (pinfunction "PC3_11") (pintype "bidirectional"))
    )
    (net (code "80") (name "unconnected-(U$2-PC4-Pad24)") (class "Default")
      (node (ref "U$2") (pin "24") (pinfunction "PC4_24") (pintype "bidirectional"))
    )
    (net (code "81") (name "unconnected-(U$3-NC-Pad5)") (class "Default")
      (node (ref "U$3") (pin "5") (pinfunction "NC_5") (pintype "no_connect"))
    )
    (net (code "82") (name "unconnected-(U1-CBUS2-Pad10)") (class "Default")
      (node (ref "U1") (pin "10") (pinfunction "CBUS2_10") (pintype "bidirectional"))
    )
    (net (code "83") (name "unconnected-(U1-CBUS3-Pad11)") (class "Default")
      (node (ref "U1") (pin "11") (pinfunction "CBUS3_11") (pintype "bidirectional"))
    )
    (net (code "84") (name "unconnected-(U1-CBUS4-Pad9)") (class "Default")
      (node (ref "U1") (pin "9") (pinfunction "CBUS4_9") (pintype "bidirectional"))
    )
    (net (code "85") (name "unconnected-(U1-CTS#-Pad8)") (class "Default")
      (node (ref "U1") (pin "8") (pinfunction "CTS#_8") (pintype "input"))
    )
    (net (code "86") (name "unconnected-(U1-DCD#-Pad7)") (class "Default")
      (node (ref "U1") (pin "7") (pinfunction "DCD#_7") (pintype "input"))
    )
    (net (code "87") (name "unconnected-(U1-DSR#-Pad6)") (class "Default")
      (node (ref "U1") (pin "6") (pinfunction "DSR#_6") (pintype "input"))
    )
    (net (code "88") (name "unconnected-(U1-DTR#-Pad31)") (class "Default")
      (node (ref "U1") (pin "31") (pinfunction "DTR#_31") (pintype "output"))
    )
    (net (code "89") (name "unconnected-(U1-OSCI-Pad27)") (class "Default")
      (node (ref "U1") (pin "27") (pinfunction "OSCI_27") (pintype "input"))
    )
    (net (code "90") (name "unconnected-(U1-OSCO-Pad28)") (class "Default")
      (node (ref "U1") (pin "28") (pinfunction "OSCO_28") (pintype "output"))
    )
    (net (code "91") (name "unconnected-(U1-RESET#-Pad18)") (class "Default")
      (node (ref "U1") (pin "18") (pinfunction "RESET#_18") (pintype "input"))
    )
    (net (code "92") (name "unconnected-(U1-RI#-Pad3)") (class "Default")
      (node (ref "U1") (pin "3") (pinfunction "RI#_3") (pintype "input"))
    )
    (net (code "93") (name "unconnected-(U1-RTS#-Pad32)") (class "Default")
      (node (ref "U1") (pin "32") (pinfunction "RTS#_32") (pintype "output"))
    )
    (net (code "94") (name "unconnected-(X5-Pad2)") (class "Default")
      (node (ref "X5") (pin "2") (pinfunction "2_2") (pintype "bidirectional"))
    )
    (net (code "95") (name "unconnected-(X5-Pad3)") (class "Default")
      (node (ref "X5") (pin "3") (pinfunction "3_3") (pintype "bidirectional"))
    )
  )
)
